# CAP-MODULE.net
KiCad netlist of a schematic drawn in EAGLE
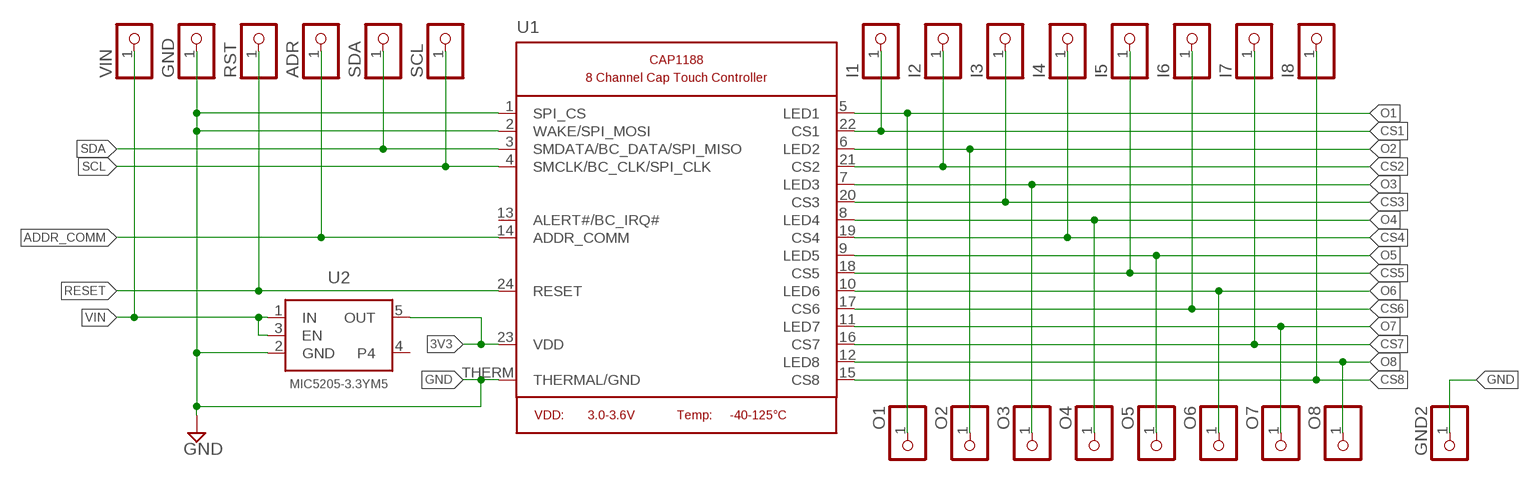
[diagram p0: schematic, sheet 1]

(export (version "E")
  (design (tool "Eeschema 10.0.6"))
  (components
    (comp (ref "ADR")
      (value "PINHD-1X1CB")
      (footprint "eagle-import:1X01-CLEANBIG")
      (libsource (lib "eagle-import") (part "PINHD-1X1CB"))
    )
    (comp (ref "GND")
      (value "PINHD-1X1CB")
      (footprint "eagle-import:1X01-CLEANBIG")
      (libsource (lib "eagle-import") (part "PINHD-1X1CB"))
    )
    (comp (ref "GND2")
      (value "PINHD-1X1CB")
      (footprint "eagle-import:1X01-CLEANBIG")
      (libsource (lib "eagle-import") (part "PINHD-1X1CB"))
    )
    (comp (ref "I1")
      (value "PINHD-1X1CB")
      (footprint "eagle-import:1X01-CLEANBIG")
      (libsource (lib "eagle-import") (part "PINHD-1X1CB"))
    )
    (comp (ref "I2")
      (value "PINHD-1X1CB")
      (footprint "eagle-import:1X01-CLEANBIG")
      (libsource (lib "eagle-import") (part "PINHD-1X1CB"))
    )
    (comp (ref "I3")
      (value "PINHD-1X1CB")
      (footprint "eagle-import:1X01-CLEANBIG")
      (libsource (lib "eagle-import") (part "PINHD-1X1CB"))
    )
    (comp (ref "I4")
      (value "PINHD-1X1CB")
      (footprint "eagle-import:1X01-CLEANBIG")
      (libsource (lib "eagle-import") (part "PINHD-1X1CB"))
    )
    (comp (ref "I5")
      (value "PINHD-1X1CB")
      (footprint "eagle-import:1X01-CLEANBIG")
      (libsource (lib "eagle-import") (part "PINHD-1X1CB"))
    )
    (comp (ref "I6")
      (value "PINHD-1X1CB")
      (footprint "eagle-import:1X01-CLEANBIG")
      (libsource (lib "eagle-import") (part "PINHD-1X1CB"))
    )
    (comp (ref "I7")
      (value "PINHD-1X1CB")
      (footprint "eagle-import:1X01-CLEANBIG")
      (libsource (lib "eagle-import") (part "PINHD-1X1CB"))
    )
    (comp (ref "I8")
      (value "PINHD-1X1CB")
      (footprint "eagle-import:1X01-CLEANBIG")
      (libsource (lib "eagle-import") (part "PINHD-1X1CB"))
    )
    (comp (ref "O1")
      (value "PINHD-1X1CB")
      (footprint "eagle-import:1X01-CLEANBIG")
      (libsource (lib "eagle-import") (part "PINHD-1X1CB"))
    )
    (comp (ref "O2")
      (value "PINHD-1X1CB")
      (footprint "eagle-import:1X01-CLEANBIG")
      (libsource (lib "eagle-import") (part "PINHD-1X1CB"))
    )
    (comp (ref "O3")
      (value "PINHD-1X1CB")
      (footprint "eagle-import:1X01-CLEANBIG")
      (libsource (lib "eagle-import") (part "PINHD-1X1CB"))
    )
    (comp (ref "O4")
      (value "PINHD-1X1CB")
      (footprint "eagle-import:1X01-CLEANBIG")
      (libsource (lib "eagle-import") (part "PINHD-1X1CB"))
    )
    (comp (ref "O5")
      (value "PINHD-1X1CB")
      (footprint "eagle-import:1X01-CLEANBIG")
      (libsource (lib "eagle-import") (part "PINHD-1X1CB"))
    )
    (comp (ref "O6")
      (value "PINHD-1X1CB")
      (footprint "eagle-import:1X01-CLEANBIG")
      (libsource (lib "eagle-import") (part "PINHD-1X1CB"))
    )
    (comp (ref "O7")
      (value "PINHD-1X1CB")
      (footprint "eagle-import:1X01-CLEANBIG")
      (libsource (lib "eagle-import") (part "PINHD-1X1CB"))
    )
    (comp (ref "O8")
      (value "PINHD-1X1CB")
      (footprint "eagle-import:1X01-CLEANBIG")
      (libsource (lib "eagle-import") (part "PINHD-1X1CB"))
    )
    (comp (ref "RST")
      (value "PINHD-1X1CB")
      (footprint "eagle-import:1X01-CLEANBIG")
      (libsource (lib "eagle-import") (part "PINHD-1X1CB"))
    )
    (comp (ref "SCL")
      (value "PINHD-1X1CB")
      (footprint "eagle-import:1X01-CLEANBIG")
      (libsource (lib "eagle-import") (part "PINHD-1X1CB"))
    )
    (comp (ref "SDA")
      (value "PINHD-1X1CB")
      (footprint "eagle-import:1X01-CLEANBIG")
      (libsource (lib "eagle-import") (part "PINHD-1X1CB"))
    )
    (comp (ref "U1")
      (value "MICROBUILDER_CAP1188")
      (footprint "eagle-import:MICROBUILDER_QFN24_4MM_SMSC")
      (libsource (lib "eagle-import") (part "MICROBUILDER_CAP1188"))
    )
    (comp (ref "U2")
      (value "MIC5205-3.3YM5")
      (footprint "eagle-import:MICROBUILDER_SOT23-5")
      (libsource (lib "eagle-import") (part "MICROBUILDER_VREG_SOT23-5"))
    )
    (comp (ref "VIN")
      (value "PINHD-1X1CB")
      (footprint "eagle-import:1X01-CLEANBIG")
      (libsource (lib "eagle-import") (part "PINHD-1X1CB"))
    )
  )
  (nets
    (net (code "1") (name "3V3") (class "Default")
      (node (ref "U1") (pin "23") (pinfunction "VDD_23") (pintype "power_in"))
      (node (ref "U2") (pin "5") (pinfunction "OUT_5") (pintype "power_in"))
    )
    (net (code "2") (name "ADDR_COMM") (class "Default")
      (node (ref "ADR") (pin "1") (pinfunction "1_1") (pintype "passive"))
      (node (ref "U1") (pin "14") (pinfunction "ADDR_COMM_14") (pintype "bidirectional"))
    )
    (net (code "3") (name "CS1") (class "Default")
      (node (ref "I1") (pin "1") (pinfunction "1_1") (pintype "passive"))
      (node (ref "U1") (pin "22") (pinfunction "CS1_22") (pintype "bidirectional"))
    )
    (net (code "4") (name "CS2") (class "Default")
      (node (ref "I2") (pin "1") (pinfunction "1_1") (pintype "passive"))
      (node (ref "U1") (pin "21") (pinfunction "CS2_21") (pintype "bidirectional"))
    )
    (net (code "5") (name "CS3") (class "Default")
      (node (ref "I3") (pin "1") (pinfunction "1_1") (pintype "passive"))
      (node (ref "U1") (pin "20") (pinfunction "CS3_20") (pintype "bidirectional"))
    )
    (net (code "6") (name "CS4") (class "Default")
      (node (ref "I4") (pin "1") (pinfunction "1_1") (pintype "passive"))
      (node (ref "U1") (pin "19") (pinfunction "CS4_19") (pintype "bidirectional"))
    )
    (net (code "7") (name "CS5") (class "Default")
      (node (ref "I5") (pin "1") (pinfunction "1_1") (pintype "passive"))
      (node (ref "U1") (pin "18") (pinfunction "CS5_18") (pintype "bidirectional"))
    )
    (net (code "8") (name "CS6") (class "Default")
      (node (ref "I6") (pin "1") (pinfunction "1_1") (pintype "passive"))
      (node (ref "U1") (pin "17") (pinfunction "CS6_17") (pintype "bidirectional"))
    )
    (net (code "9") (name "CS7") (class "Default")
      (node (ref "I7") (pin "1") (pinfunction "1_1") (pintype "passive"))
      (node (ref "U1") (pin "16") (pinfunction "CS7_16") (pintype "bidirectional"))
    )
    (net (code "10") (name "CS8") (class "Default")
      (node (ref "I8") (pin "1") (pinfunction "1_1") (pintype "passive"))
      (node (ref "U1") (pin "15") (pinfunction "CS8_15") (pintype "bidirectional"))
    )
    (net (code "11") (name "GND") (class "Default")
      (node (ref "GND") (pin "1") (pinfunction "1_1") (pintype "passive"))
      (node (ref "GND2") (pin "1") (pinfunction "1_1") (pintype "passive"))
      (node (ref "U1") (pin "1") (pinfunction "SPI_CS_1") (pintype "input"))
      (node (ref "U1") (pin "2") (pinfunction "WAKE/SPI_MOSI_2") (pintype "bidirectional"))
      (node (ref "U1") (pin "THERM") (pinfunction "THERMAL/GND_THERM") (pintype "power_in"))
      (node (ref "U2") (pin "2") (pinfunction "GND_2") (pintype "power_in"))
    )
    (net (code "12") (name "O1") (class "Default")
      (node (ref "O1") (pin "1") (pinfunction "1_1") (pintype "passive"))
      (node (ref "U1") (pin "5") (pinfunction "LED1_5") (pintype "bidirectional"))
    )
    (net (code "13") (name "O2") (class "Default")
      (node (ref "O2") (pin "1") (pinfunction "1_1") (pintype "passive"))
      (node (ref "U1") (pin "6") (pinfunction "LED2_6") (pintype "bidirectional"))
    )
    (net (code "14") (name "O3") (class "Default")
      (node (ref "O3") (pin "1") (pinfunction "1_1") (pintype "passive"))
      (node (ref "U1") (pin "7") (pinfunction "LED3_7") (pintype "bidirectional"))
    )
    (net (code "15") (name "O4") (class "Default")
      (node (ref "O4") (pin "1") (pinfunction "1_1") (pintype "passive"))
      (node (ref "U1") (pin "8") (pinfunction "LED4_8") (pintype "bidirectional"))
    )
    (net (code "16") (name "O5") (class "Default")
      (node (ref "O5") (pin "1") (pinfunction "1_1") (pintype "passive"))
      (node (ref "U1") (pin "9") (pinfunction "LED5_9") (pintype "bidirectional"))
    )
    (net (code "17") (name "O6") (class "Default")
      (node (ref "O6") (pin "1") (pinfunction "1_1") (pintype "passive"))
      (node (ref "U1") (pin "10") (pinfunction "LED6_10") (pintype "bidirectional"))
    )
    (net (code "18") (name "O7") (class "Default")
      (node (ref "O7") (pin "1") (pinfunction "1_1") (pintype "passive"))
      (node (ref "U1") (pin "11") (pinfunction "LED7_11") (pintype "bidirectional"))
    )
    (net (code "19") (name "O8") (class "Default")
      (node (ref "O8") (pin "1") (pinfunction "1_1") (pintype "passive"))
      (node (ref "U1") (pin "12") (pinfunction "LED8_12") (pintype "bidirectional"))
    )
    (net (code "20") (name "RESET") (class "Default")
      (node (ref "RST") (pin "1") (pinfunction "1_1") (pintype "passive"))
      (node (ref "U1") (pin "24") (pinfunction "RESET_24") (pintype "input"))
    )
    (net (code "21") (name "SCL") (class "Default")
      (node (ref "SCL") (pin "1") (pinfunction "1_1") (pintype "passive"))
      (node (ref "U1") (pin "4") (pinfunction "SMCLK/BC_CLK/SPI_CLK_4") (pintype "bidirectional"))
    )
    (net (code "22") (name "SDA") (class "Default")
      (node (ref "SDA") (pin "1") (pinfunction "1_1") (pintype "passive"))
      (node (ref "U1") (pin "3") (pinfunction "SMDATA/BC_DATA/SPI_MISO_3") (pintype "bidirectional"))
    )
    (net (code "23") (name "VIN") (class "Default")
      (node (ref "U2") (pin "1") (pinfunction "IN_1") (pintype "power_in"))
      (node (ref "U2") (pin "3") (pinfunction "EN_3") (pintype "input"))
      (node (ref "VIN") (pin "1") (pinfunction "1_1") (pintype "passive"))
    )
    (net (code "24") (name "unconnected-(U1-ALERT#{slash}BC_IRQ#-Pad13)") (class "Default")
      (node (ref "U1") (pin "13") (pinfunction "ALERT#/BC_IRQ#_13") (pintype "bidirectional"))
    )
    (net (code "25") (name "unconnected-(U2-P4-Pad4)") (class "Default")
      (node (ref "U2") (pin "4") (pinfunction "P4_4") (pintype "bidirectional"))
    )
  )
)
